# eeZeeRGBTestJig.net
KiCad netlist of a schematic drawn in EAGLE
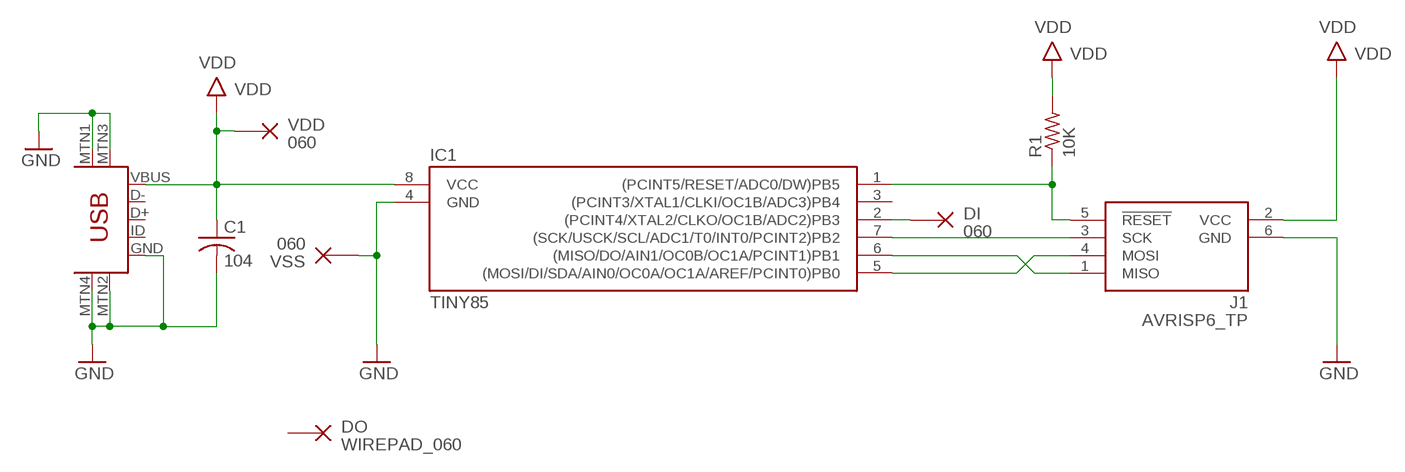
[diagram p0: schematic, sheet 1]

(export (version "E")
  (design (tool "Eeschema 10.0.6"))
  (components
    (comp (ref "C1")
      (value "104")
      (footprint "eagle-import:C0603")
      (libsource (lib "eagle-import") (part "C-USC0603"))
    )
    (comp (ref "DI")
      (value "060")
      (footprint "eagle-import:PAD_060")
      (libsource (lib "eagle-import") (part "WIREPAD_060"))
    )
    (comp (ref "DO")
      (value "WIREPAD_060")
      (footprint "eagle-import:PAD_060")
      (libsource (lib "eagle-import") (part "WIREPAD_060"))
    )
    (comp (ref "IC1")
      (value "TINY85")
      (footprint "eagle-import:SOIC8N")
      (libsource (lib "eagle-import") (part "TINY25/45/85-20SSU"))
    )
    (comp (ref "J1")
      (value "AVRISP6_TP")
      (footprint "eagle-import:2X3_TP")
      (libsource (lib "eagle-import") (part "AVRISP6_TP"))
    )
    (comp (ref "R1")
      (value "10K")
      (footprint "eagle-import:R0603")
      (libsource (lib "eagle-import") (part "R-US_R0603"))
    )
    (comp (ref "U$1")
      (value "USB-MINIB-5PIN")
      (footprint "eagle-import:USB-MINIB")
      (libsource (lib "eagle-import") (part "USB-MINIB-5PIN"))
    )
    (comp (ref "VDD")
      (value "060")
      (footprint "eagle-import:PAD_060")
      (libsource (lib "eagle-import") (part "WIREPAD_060"))
    )
    (comp (ref "VSS")
      (value "060")
      (footprint "eagle-import:PAD_060")
      (libsource (lib "eagle-import") (part "WIREPAD_060"))
    )
  )
  (nets
    (net (code "1") (name "GND") (class "Default")
      (node (ref "C1") (pin "2") (pinfunction "2_2") (pintype "passive"))
      (node (ref "IC1") (pin "4") (pinfunction "GND_4") (pintype "power_in"))
      (node (ref "J1") (pin "6") (pinfunction "GND_6") (pintype "power_in"))
      (node (ref "U$1") (pin "GND") (pinfunction "GND_GND") (pintype "bidirectional"))
      (node (ref "U$1") (pin "MTN1") (pinfunction "MTN2_MTN1") (pintype "bidirectional"))
      (node (ref "U$1") (pin "MTN2") (pinfunction "MTN3_MTN2") (pintype "bidirectional"))
      (node (ref "U$1") (pin "MTN3") (pinfunction "MTN1_MTN3") (pintype "bidirectional"))
      (node (ref "U$1") (pin "MTN4") (pinfunction "MTN4_MTN4") (pintype "bidirectional"))
      (node (ref "VSS") (pin "P$1") (pinfunction "P_P$1") (pintype "bidirectional"))
    )
    (net (code "2") (name "Net-(DI-P)") (class "Default")
      (node (ref "DI") (pin "P$1") (pinfunction "P_P$1") (pintype "bidirectional"))
      (node (ref "IC1") (pin "2") (pinfunction "(PCINT4/XTAL2/CLKO/OC1B/ADC2)PB3_2") (pintype "bidirectional"))
    )
    (net (code "3") (name "Net-(IC1-(MISO{slash}DO{slash}AIN1{slash}OC0B{slash}OC1A{slash}PCINT1)PB1)") (class "Default")
      (node (ref "IC1") (pin "6") (pinfunction "(MISO/DO/AIN1/OC0B/OC1A/PCINT1)PB1_6") (pintype "bidirectional"))
      (node (ref "J1") (pin "1") (pinfunction "MISO_1") (pintype "input"))
    )
    (net (code "4") (name "Net-(IC1-(MOSI{slash}DI{slash}SDA{slash}AIN0{slash}OC0A{slash}OC1A{slash}AREF{slash}PCINT0)PB0)") (class "Default")
      (node (ref "IC1") (pin "5") (pinfunction "(MOSI/DI/SDA/AIN0/OC0A/OC1A/AREF/PCINT0)PB0_5") (pintype "bidirectional"))
      (node (ref "J1") (pin "4") (pinfunction "MOSI_4") (pintype "output"))
    )
    (net (code "5") (name "Net-(IC1-(PCINT5{slash}RESET{slash}ADC0{slash}DW)PB5)") (class "Default")
      (node (ref "IC1") (pin "1") (pinfunction "(PCINT5/RESET/ADC0/DW)PB5_1") (pintype "bidirectional"))
      (node (ref "J1") (pin "5") (pinfunction "~{RESET}_5") (pintype "output"))
      (node (ref "R1") (pin "1") (pinfunction "1_1") (pintype "passive"))
    )
    (net (code "6") (name "Net-(IC1-(SCK{slash}USCK{slash}SCL{slash}ADC1{slash}T0{slash}INT0{slash}PCINT2)PB2)") (class "Default")
      (node (ref "IC1") (pin "7") (pinfunction "(SCK/USCK/SCL/ADC1/T0/INT0/PCINT2)PB2_7") (pintype "bidirectional"))
      (node (ref "J1") (pin "3") (pinfunction "SCK_3") (pintype "output"))
    )
    (net (code "7") (name "VDD") (class "Default")
      (node (ref "C1") (pin "1") (pinfunction "1_1") (pintype "passive"))
      (node (ref "IC1") (pin "8") (pinfunction "VCC_8") (pintype "power_in"))
      (node (ref "J1") (pin "2") (pinfunction "VCC_2") (pintype "power_in"))
      (node (ref "R1") (pin "2") (pinfunction "2_2") (pintype "passive"))
      (node (ref "U$1") (pin "VBUS") (pinfunction "VBUS_VBUS") (pintype "bidirectional"))
      (node (ref "VDD") (pin "P$1") (pinfunction "P_P$1") (pintype "bidirectional"))
    )
    (net (code "8") (name "unconnected-(DO-P-PadP$1)") (class "Default")
      (node (ref "DO") (pin "P$1") (pinfunction "P_P$1") (pintype "bidirectional"))
    )
    (net (code "9") (name "unconnected-(IC1-(PCINT3{slash}XTAL1{slash}CLKI{slash}OC1B{slash}ADC3)PB4-Pad3)") (class "Default")
      (node (ref "IC1") (pin "3") (pinfunction "(PCINT3/XTAL1/CLKI/OC1B/ADC3)PB4_3") (pintype "bidirectional"))
    )
    (net (code "10") (name "unconnected-(U$1-PadD+)") (class "Default")
      (node (ref "U$1") (pin "D+") (pinfunction "D+_D+") (pintype "bidirectional"))
    )
    (net (code "11") (name "unconnected-(U$1-PadD-)") (class "Default")
      (node (ref "U$1") (pin "D-") (pinfunction "D-_D-") (pintype "bidirectional"))
    )
    (net (code "12") (name "unconnected-(U$1-PadID)") (class "Default")
      (node (ref "U$1") (pin "ID") (pinfunction "ID_ID") (pintype "bidirectional"))
    )
  )
)
